# teste01.net
KiCad netlist of a schematic drawn in EAGLE
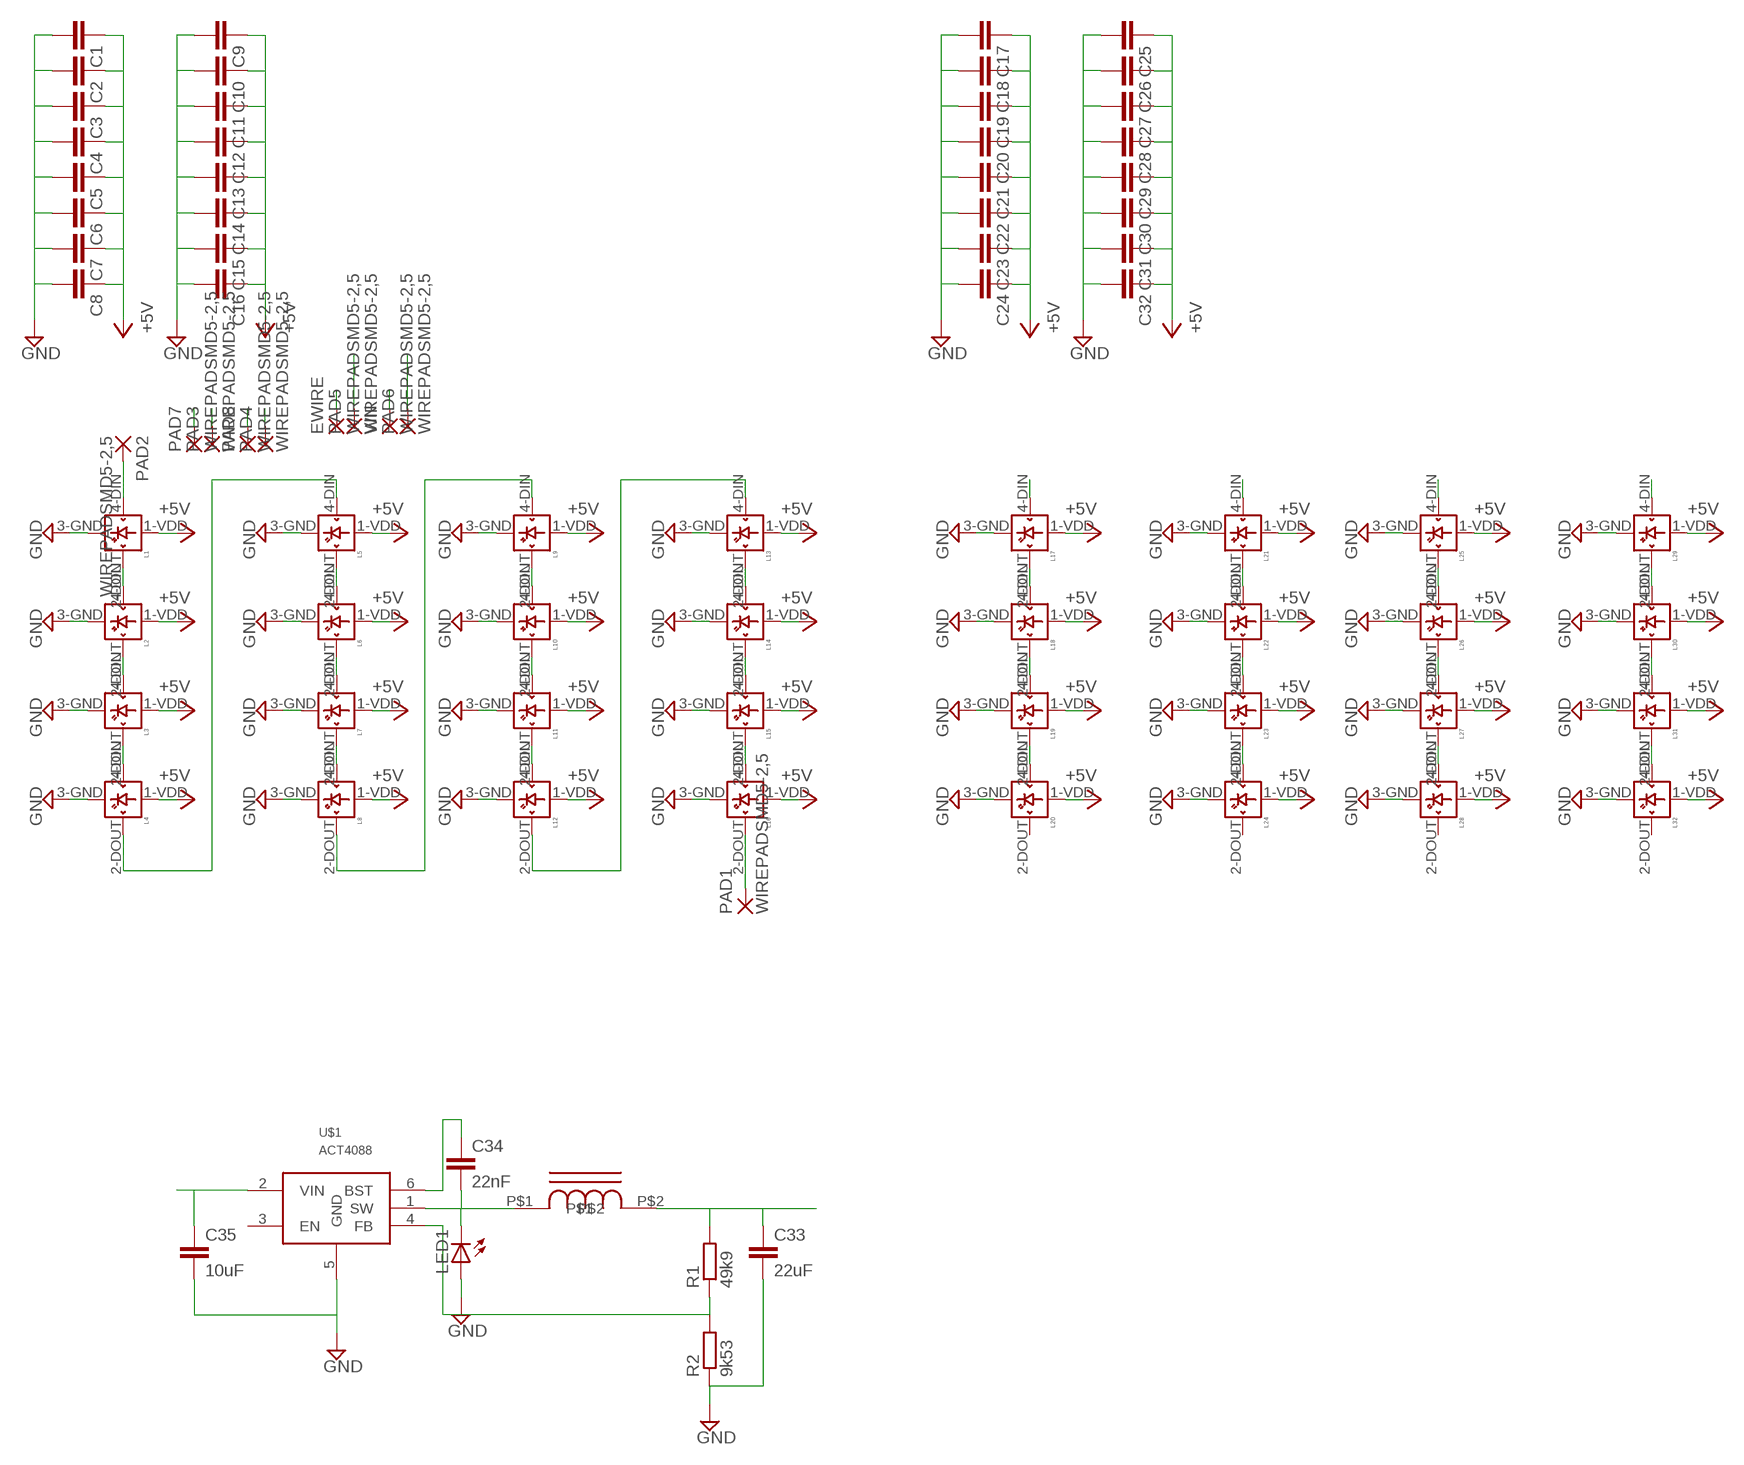
[diagram p0: schematic, sheet 1]

(export (version "E")
  (design (tool "Eeschema 10.0.6"))
  (components
    (comp (ref "C1")
      (value "C-EUC0805K")
      (footprint "eagle-import:C0805K")
      (libsource (lib "eagle-import") (part "resistor_C-EUC0805K"))
    )
    (comp (ref "C2")
      (value "C-EUC0805K")
      (footprint "eagle-import:C0805K")
      (libsource (lib "eagle-import") (part "resistor_C-EUC0805K"))
    )
    (comp (ref "C3")
      (value "C-EUC0805K")
      (footprint "eagle-import:C0805K")
      (libsource (lib "eagle-import") (part "resistor_C-EUC0805K"))
    )
    (comp (ref "C4")
      (value "C-EUC0805K")
      (footprint "eagle-import:C0805K")
      (libsource (lib "eagle-import") (part "resistor_C-EUC0805K"))
    )
    (comp (ref "C5")
      (value "C-EUC0805K")
      (footprint "eagle-import:C0805K")
      (libsource (lib "eagle-import") (part "resistor_C-EUC0805K"))
    )
    (comp (ref "C6")
      (value "C-EUC0805K")
      (footprint "eagle-import:C0805K")
      (libsource (lib "eagle-import") (part "resistor_C-EUC0805K"))
    )
    (comp (ref "C7")
      (value "C-EUC0805K")
      (footprint "eagle-import:C0805K")
      (libsource (lib "eagle-import") (part "resistor_C-EUC0805K"))
    )
    (comp (ref "C8")
      (value "C-EUC0805K")
      (footprint "eagle-import:C0805K")
      (libsource (lib "eagle-import") (part "resistor_C-EUC0805K"))
    )
    (comp (ref "C9")
      (value "C-EUC0805K")
      (footprint "eagle-import:C0805K")
      (libsource (lib "eagle-import") (part "resistor_C-EUC0805K"))
    )
    (comp (ref "C10")
      (value "C-EUC0805K")
      (footprint "eagle-import:C0805K")
      (libsource (lib "eagle-import") (part "resistor_C-EUC0805K"))
    )
    (comp (ref "C11")
      (value "C-EUC0805K")
      (footprint "eagle-import:C0805K")
      (libsource (lib "eagle-import") (part "resistor_C-EUC0805K"))
    )
    (comp (ref "C12")
      (value "C-EUC0805K")
      (footprint "eagle-import:C0805K")
      (libsource (lib "eagle-import") (part "resistor_C-EUC0805K"))
    )
    (comp (ref "C13")
      (value "C-EUC0805K")
      (footprint "eagle-import:C0805K")
      (libsource (lib "eagle-import") (part "resistor_C-EUC0805K"))
    )
    (comp (ref "C14")
      (value "C-EUC0805K")
      (footprint "eagle-import:C0805K")
      (libsource (lib "eagle-import") (part "resistor_C-EUC0805K"))
    )
    (comp (ref "C15")
      (value "C-EUC0805K")
      (footprint "eagle-import:C0805K")
      (libsource (lib "eagle-import") (part "resistor_C-EUC0805K"))
    )
    (comp (ref "C16")
      (value "C-EUC0805K")
      (footprint "eagle-import:C0805K")
      (libsource (lib "eagle-import") (part "resistor_C-EUC0805K"))
    )
    (comp (ref "C17")
      (value "C-EUC0805K")
      (footprint "eagle-import:C0805K")
      (libsource (lib "eagle-import") (part "resistor_C-EUC0805K"))
    )
    (comp (ref "C18")
      (value "C-EUC0805K")
      (footprint "eagle-import:C0805K")
      (libsource (lib "eagle-import") (part "resistor_C-EUC0805K"))
    )
    (comp (ref "C19")
      (value "C-EUC0805K")
      (footprint "eagle-import:C0805K")
      (libsource (lib "eagle-import") (part "resistor_C-EUC0805K"))
    )
    (comp (ref "C20")
      (value "C-EUC0805K")
      (footprint "eagle-import:C0805K")
      (libsource (lib "eagle-import") (part "resistor_C-EUC0805K"))
    )
    (comp (ref "C21")
      (value "C-EUC0805K")
      (footprint "eagle-import:C0805K")
      (libsource (lib "eagle-import") (part "resistor_C-EUC0805K"))
    )
    (comp (ref "C22")
      (value "C-EUC0805K")
      (footprint "eagle-import:C0805K")
      (libsource (lib "eagle-import") (part "resistor_C-EUC0805K"))
    )
    (comp (ref "C23")
      (value "C-EUC0805K")
      (footprint "eagle-import:C0805K")
      (libsource (lib "eagle-import") (part "resistor_C-EUC0805K"))
    )
    (comp (ref "C24")
      (value "C-EUC0805K")
      (footprint "eagle-import:C0805K")
      (libsource (lib "eagle-import") (part "resistor_C-EUC0805K"))
    )
    (comp (ref "C25")
      (value "C-EUC0805K")
      (footprint "eagle-import:C0805K")
      (libsource (lib "eagle-import") (part "resistor_C-EUC0805K"))
    )
    (comp (ref "C26")
      (value "C-EUC0805K")
      (footprint "eagle-import:C0805K")
      (libsource (lib "eagle-import") (part "resistor_C-EUC0805K"))
    )
    (comp (ref "C27")
      (value "C-EUC0805K")
      (footprint "eagle-import:C0805K")
      (libsource (lib "eagle-import") (part "resistor_C-EUC0805K"))
    )
    (comp (ref "C28")
      (value "C-EUC0805K")
      (footprint "eagle-import:C0805K")
      (libsource (lib "eagle-import") (part "resistor_C-EUC0805K"))
    )
    (comp (ref "C29")
      (value "C-EUC0805K")
      (footprint "eagle-import:C0805K")
      (libsource (lib "eagle-import") (part "resistor_C-EUC0805K"))
    )
    (comp (ref "C30")
      (value "C-EUC0805K")
      (footprint "eagle-import:C0805K")
      (libsource (lib "eagle-import") (part "resistor_C-EUC0805K"))
    )
    (comp (ref "C31")
      (value "C-EUC0805K")
      (footprint "eagle-import:C0805K")
      (libsource (lib "eagle-import") (part "resistor_C-EUC0805K"))
    )
    (comp (ref "C32")
      (value "C-EUC0805K")
      (footprint "eagle-import:C0805K")
      (libsource (lib "eagle-import") (part "resistor_C-EUC0805K"))
    )
    (comp (ref "C33")
      (value "22uF")
      (footprint "eagle-import:C1210")
      (libsource (lib "eagle-import") (part "C-EUC1210"))
    )
    (comp (ref "C34")
      (value "22nF")
      (footprint "eagle-import:C0805")
      (libsource (lib "eagle-import") (part "resistor_C-EUC0805"))
    )
    (comp (ref "C35")
      (value "10uF")
      (footprint "eagle-import:C1210")
      (libsource (lib "eagle-import") (part "C-EUC1210"))
    )
    (comp (ref "EWIRE")
      (value "WIREPADSMD5-2,5")
      (footprint "eagle-import:5-2,5")
      (libsource (lib "eagle-import") (part "WIREPADSMD5-2,5"))
    )
    (comp (ref "L1")
      (value "WS2812B")
      (footprint "eagle-import:WS2812B")
      (libsource (lib "eagle-import") (part "WS2812B"))
    )
    (comp (ref "L2")
      (value "WS2812B")
      (footprint "eagle-import:WS2812B")
      (libsource (lib "eagle-import") (part "WS2812B"))
    )
    (comp (ref "L3")
      (value "WS2812B")
      (footprint "eagle-import:WS2812B")
      (libsource (lib "eagle-import") (part "WS2812B"))
    )
    (comp (ref "L4")
      (value "WS2812B")
      (footprint "eagle-import:WS2812B")
      (libsource (lib "eagle-import") (part "WS2812B"))
    )
    (comp (ref "L5")
      (value "WS2812B")
      (footprint "eagle-import:WS2812B")
      (libsource (lib "eagle-import") (part "WS2812B"))
    )
    (comp (ref "L6")
      (value "WS2812B")
      (footprint "eagle-import:WS2812B")
      (libsource (lib "eagle-import") (part "WS2812B"))
    )
    (comp (ref "L7")
      (value "WS2812B")
      (footprint "eagle-import:WS2812B")
      (libsource (lib "eagle-import") (part "WS2812B"))
    )
    (comp (ref "L8")
      (value "WS2812B")
      (footprint "eagle-import:WS2812B")
      (libsource (lib "eagle-import") (part "WS2812B"))
    )
    (comp (ref "L9")
      (value "WS2812B")
      (footprint "eagle-import:WS2812B")
      (libsource (lib "eagle-import") (part "WS2812B"))
    )
    (comp (ref "L10")
      (value "WS2812B")
      (footprint "eagle-import:WS2812B")
      (libsource (lib "eagle-import") (part "WS2812B"))
    )
    (comp (ref "L11")
      (value "WS2812B")
      (footprint "eagle-import:WS2812B")
      (libsource (lib "eagle-import") (part "WS2812B"))
    )
    (comp (ref "L12")
      (value "WS2812B")
      (footprint "eagle-import:WS2812B")
      (libsource (lib "eagle-import") (part "WS2812B"))
    )
    (comp (ref "L13")
      (value "WS2812B")
      (footprint "eagle-import:WS2812B")
      (libsource (lib "eagle-import") (part "WS2812B"))
    )
    (comp (ref "L14")
      (value "WS2812B")
      (footprint "eagle-import:WS2812B")
      (libsource (lib "eagle-import") (part "WS2812B"))
    )
    (comp (ref "L15")
      (value "WS2812B")
      (footprint "eagle-import:WS2812B")
      (libsource (lib "eagle-import") (part "WS2812B"))
    )
    (comp (ref "L16")
      (value "WS2812B")
      (footprint "eagle-import:WS2812B")
      (libsource (lib "eagle-import") (part "WS2812B"))
    )
    (comp (ref "L17")
      (value "WS2812B")
      (footprint "eagle-import:WS2812B")
      (libsource (lib "eagle-import") (part "WS2812B"))
    )
    (comp (ref "L18")
      (value "WS2812B")
      (footprint "eagle-import:WS2812B")
      (libsource (lib "eagle-import") (part "WS2812B"))
    )
    (comp (ref "L19")
      (value "WS2812B")
      (footprint "eagle-import:WS2812B")
      (libsource (lib "eagle-import") (part "WS2812B"))
    )
    (comp (ref "L20")
      (value "WS2812B")
      (footprint "eagle-import:WS2812B")
      (libsource (lib "eagle-import") (part "WS2812B"))
    )
    (comp (ref "L21")
      (value "WS2812B")
      (footprint "eagle-import:WS2812B")
      (libsource (lib "eagle-import") (part "WS2812B"))
    )
    (comp (ref "L22")
      (value "WS2812B")
      (footprint "eagle-import:WS2812B")
      (libsource (lib "eagle-import") (part "WS2812B"))
    )
    (comp (ref "L23")
      (value "WS2812B")
      (footprint "eagle-import:WS2812B")
      (libsource (lib "eagle-import") (part "WS2812B"))
    )
    (comp (ref "L24")
      (value "WS2812B")
      (footprint "eagle-import:WS2812B")
      (libsource (lib "eagle-import") (part "WS2812B"))
    )
    (comp (ref "L25")
      (value "WS2812B")
      (footprint "eagle-import:WS2812B")
      (libsource (lib "eagle-import") (part "WS2812B"))
    )
    (comp (ref "L26")
      (value "WS2812B")
      (footprint "eagle-import:WS2812B")
      (libsource (lib "eagle-import") (part "WS2812B"))
    )
    (comp (ref "L27")
      (value "WS2812B")
      (footprint "eagle-import:WS2812B")
      (libsource (lib "eagle-import") (part "WS2812B"))
    )
    (comp (ref "L28")
      (value "WS2812B")
      (footprint "eagle-import:WS2812B")
      (libsource (lib "eagle-import") (part "WS2812B"))
    )
    (comp (ref "L29")
      (value "WS2812B")
      (footprint "eagle-import:WS2812B")
      (libsource (lib "eagle-import") (part "WS2812B"))
    )
    (comp (ref "L30")
      (value "WS2812B")
      (footprint "eagle-import:WS2812B")
      (libsource (lib "eagle-import") (part "WS2812B"))
    )
    (comp (ref "L31")
      (value "WS2812B")
      (footprint "eagle-import:WS2812B")
      (libsource (lib "eagle-import") (part "WS2812B"))
    )
    (comp (ref "L32")
      (value "WS2812B")
      (footprint "eagle-import:WS2812B")
      (libsource (lib "eagle-import") (part "WS2812B"))
    )
    (comp (ref "LED1")
      (value "LED1206")
      (footprint "eagle-import:LED-1206")
      (libsource (lib "eagle-import") (part "LED1206"))
    )
    (comp (ref "PAD1")
      (value "WIREPADSMD5-2,5")
      (footprint "eagle-import:5-2,5")
      (libsource (lib "eagle-import") (part "WIREPADSMD5-2,5"))
    )
    (comp (ref "PAD2")
      (value "WIREPADSMD5-2,5")
      (footprint "eagle-import:5-2,5")
      (libsource (lib "eagle-import") (part "WIREPADSMD5-2,5"))
    )
    (comp (ref "PAD3")
      (value "WIREPADSMD5-2,5")
      (footprint "eagle-import:5-2,5")
      (libsource (lib "eagle-import") (part "WIREPADSMD5-2,5"))
    )
    (comp (ref "PAD4")
      (value "WIREPADSMD5-2,5")
      (footprint "eagle-import:5-2,5")
      (libsource (lib "eagle-import") (part "WIREPADSMD5-2,5"))
    )
    (comp (ref "PAD5")
      (value "WIREPADSMD5-2,5")
      (footprint "eagle-import:5-2,5")
      (libsource (lib "eagle-import") (part "WIREPADSMD5-2,5"))
    )
    (comp (ref "PAD6")
      (value "WIREPADSMD5-2,5")
      (footprint "eagle-import:5-2,5")
      (libsource (lib "eagle-import") (part "WIREPADSMD5-2,5"))
    )
    (comp (ref "PAD7")
      (value "WIREPADSMD5-2,5")
      (footprint "eagle-import:5-2,5")
      (libsource (lib "eagle-import") (part "WIREPADSMD5-2,5"))
    )
    (comp (ref "PAD8")
      (value "WIREPADSMD5-2,5")
      (footprint "eagle-import:5-2,5")
      (libsource (lib "eagle-import") (part "WIREPADSMD5-2,5"))
    )
    (comp (ref "R1")
      (value "49k9")
      (footprint "eagle-import:M0805")
      (libsource (lib "eagle-import") (part "R-EU_M0805"))
    )
    (comp (ref "R2")
      (value "9k53")
      (footprint "eagle-import:M0805")
      (libsource (lib "eagle-import") (part "R-EU_M0805"))
    )
    (comp (ref "U$1")
      (value "ACT4088")
      (footprint "eagle-import:SOT23-6")
      (libsource (lib "eagle-import") (part "ACT4088"))
    )
    (comp (ref "U$2")
      (value "INDUCTOR")
      (footprint "eagle-import:6060")
      (libsource (lib "eagle-import") (part "INDUCTOR"))
    )
    (comp (ref "VIN")
      (value "WIREPADSMD5-2,5")
      (footprint "eagle-import:5-2,5")
      (libsource (lib "eagle-import") (part "WIREPADSMD5-2,5"))
    )
  )
  (nets
    (net (code "1") (name "+5V") (class "Default")
      (node (ref "C1") (pin "1") (pinfunction "1_1") (pintype "passive"))
      (node (ref "C10") (pin "1") (pinfunction "1_1") (pintype "passive"))
      (node (ref "C11") (pin "1") (pinfunction "1_1") (pintype "passive"))
      (node (ref "C12") (pin "1") (pinfunction "1_1") (pintype "passive"))
      (node (ref "C13") (pin "1") (pinfunction "1_1") (pintype "passive"))
      (node (ref "C14") (pin "1") (pinfunction "1_1") (pintype "passive"))
      (node (ref "C15") (pin "1") (pinfunction "1_1") (pintype "passive"))
      (node (ref "C16") (pin "1") (pinfunction "1_1") (pintype "passive"))
      (node (ref "C17") (pin "1") (pinfunction "1_1") (pintype "passive"))
      (node (ref "C18") (pin "1") (pinfunction "1_1") (pintype "passive"))
      (node (ref "C19") (pin "1") (pinfunction "1_1") (pintype "passive"))
      (node (ref "C2") (pin "1") (pinfunction "1_1") (pintype "passive"))
      (node (ref "C20") (pin "1") (pinfunction "1_1") (pintype "passive"))
      (node (ref "C21") (pin "1") (pinfunction "1_1") (pintype "passive"))
      (node (ref "C22") (pin "1") (pinfunction "1_1") (pintype "passive"))
      (node (ref "C23") (pin "1") (pinfunction "1_1") (pintype "passive"))
      (node (ref "C24") (pin "1") (pinfunction "1_1") (pintype "passive"))
      (node (ref "C25") (pin "1") (pinfunction "1_1") (pintype "passive"))
      (node (ref "C26") (pin "1") (pinfunction "1_1") (pintype "passive"))
      (node (ref "C27") (pin "1") (pinfunction "1_1") (pintype "passive"))
      (node (ref "C28") (pin "1") (pinfunction "1_1") (pintype "passive"))
      (node (ref "C29") (pin "1") (pinfunction "1_1") (pintype "passive"))
      (node (ref "C3") (pin "1") (pinfunction "1_1") (pintype "passive"))
      (node (ref "C30") (pin "1") (pinfunction "1_1") (pintype "passive"))
      (node (ref "C31") (pin "1") (pinfunction "1_1") (pintype "passive"))
      (node (ref "C32") (pin "1") (pinfunction "1_1") (pintype "passive"))
      (node (ref "C4") (pin "1") (pinfunction "1_1") (pintype "passive"))
      (node (ref "C5") (pin "1") (pinfunction "1_1") (pintype "passive"))
      (node (ref "C6") (pin "1") (pinfunction "1_1") (pintype "passive"))
      (node (ref "C7") (pin "1") (pinfunction "1_1") (pintype "passive"))
      (node (ref "C8") (pin "1") (pinfunction "1_1") (pintype "passive"))
      (node (ref "C9") (pin "1") (pinfunction "1_1") (pintype "passive"))
      (node (ref "L1") (pin "1-VDD") (pinfunction "VDD_1-VDD") (pintype "bidirectional"))
      (node (ref "L10") (pin "1-VDD") (pinfunction "VDD_1-VDD") (pintype "bidirectional"))
      (node (ref "L11") (pin "1-VDD") (pinfunction "VDD_1-VDD") (pintype "bidirectional"))
      (node (ref "L12") (pin "1-VDD") (pinfunction "VDD_1-VDD") (pintype "bidirectional"))
      (node (ref "L13") (pin "1-VDD") (pinfunction "VDD_1-VDD") (pintype "bidirectional"))
      (node (ref "L14") (pin "1-VDD") (pinfunction "VDD_1-VDD") (pintype "bidirectional"))
      (node (ref "L15") (pin "1-VDD") (pinfunction "VDD_1-VDD") (pintype "bidirectional"))
      (node (ref "L16") (pin "1-VDD") (pinfunction "VDD_1-VDD") (pintype "bidirectional"))
      (node (ref "L17") (pin "1-VDD") (pinfunction "VDD_1-VDD") (pintype "bidirectional"))
      (node (ref "L18") (pin "1-VDD") (pinfunction "VDD_1-VDD") (pintype "bidirectional"))
      (node (ref "L19") (pin "1-VDD") (pinfunction "VDD_1-VDD") (pintype "bidirectional"))
      (node (ref "L2") (pin "1-VDD") (pinfunction "VDD_1-VDD") (pintype "bidirectional"))
      (node (ref "L20") (pin "1-VDD") (pinfunction "VDD_1-VDD") (pintype "bidirectional"))
      (node (ref "L21") (pin "1-VDD") (pinfunction "VDD_1-VDD") (pintype "bidirectional"))
      (node (ref "L22") (pin "1-VDD") (pinfunction "VDD_1-VDD") (pintype "bidirectional"))
      (node (ref "L23") (pin "1-VDD") (pinfunction "VDD_1-VDD") (pintype "bidirectional"))
      (node (ref "L24") (pin "1-VDD") (pinfunction "VDD_1-VDD") (pintype "bidirectional"))
      (node (ref "L25") (pin "1-VDD") (pinfunction "VDD_1-VDD") (pintype "bidirectional"))
      (node (ref "L26") (pin "1-VDD") (pinfunction "VDD_1-VDD") (pintype "bidirectional"))
      (node (ref "L27") (pin "1-VDD") (pinfunction "VDD_1-VDD") (pintype "bidirectional"))
      (node (ref "L28") (pin "1-VDD") (pinfunction "VDD_1-VDD") (pintype "bidirectional"))
      (node (ref "L29") (pin "1-VDD") (pinfunction "VDD_1-VDD") (pintype "bidirectional"))
      (node (ref "L3") (pin "1-VDD") (pinfunction "VDD_1-VDD") (pintype "bidirectional"))
      (node (ref "L30") (pin "1-VDD") (pinfunction "VDD_1-VDD") (pintype "bidirectional"))
      (node (ref "L31") (pin "1-VDD") (pinfunction "VDD_1-VDD") (pintype "bidirectional"))
      (node (ref "L32") (pin "1-VDD") (pinfunction "VDD_1-VDD") (pintype "bidirectional"))
      (node (ref "L4") (pin "1-VDD") (pinfunction "VDD_1-VDD") (pintype "bidirectional"))
      (node (ref "L5") (pin "1-VDD") (pinfunction "VDD_1-VDD") (pintype "bidirectional"))
      (node (ref "L6") (pin "1-VDD") (pinfunction "VDD_1-VDD") (pintype "bidirectional"))
      (node (ref "L7") (pin "1-VDD") (pinfunction "VDD_1-VDD") (pintype "bidirectional"))
      (node (ref "L8") (pin "1-VDD") (pinfunction "VDD_1-VDD") (pintype "bidirectional"))
      (node (ref "L9") (pin "1-VDD") (pinfunction "VDD_1-VDD") (pintype "bidirectional"))
    )
    (net (code "2") (name "/VIN") (class "Default")
      (node (ref "C35") (pin "1") (pinfunction "1_1") (pintype "passive"))
      (node (ref "EWIRE") (pin "1") (pinfunction "P_1") (pintype "passive"))
      (node (ref "PAD5") (pin "1") (pinfunction "P_1") (pintype "passive"))
      (node (ref "PAD6") (pin "1") (pinfunction "P_1") (pintype "passive"))
      (node (ref "U$1") (pin "2") (pinfunction "VIN_2") (pintype "bidirectional"))
      (node (ref "VIN") (pin "1") (pinfunction "P_1") (pintype "passive"))
    )
    (net (code "3") (name "GND") (class "Default")
      (node (ref "C1") (pin "2") (pinfunction "2_2") (pintype "passive"))
      (node (ref "C10") (pin "2") (pinfunction "2_2") (pintype "passive"))
      (node (ref "C11") (pin "2") (pinfunction "2_2") (pintype "passive"))
      (node (ref "C12") (pin "2") (pinfunction "2_2") (pintype "passive"))
      (node (ref "C13") (pin "2") (pinfunction "2_2") (pintype "passive"))
      (node (ref "C14") (pin "2") (pinfunction "2_2") (pintype "passive"))
      (node (ref "C15") (pin "2") (pinfunction "2_2") (pintype "passive"))
      (node (ref "C16") (pin "2") (pinfunction "2_2") (pintype "passive"))
      (node (ref "C17") (pin "2") (pinfunction "2_2") (pintype "passive"))
      (node (ref "C18") (pin "2") (pinfunction "2_2") (pintype "passive"))
      (node (ref "C19") (pin "2") (pinfunction "2_2") (pintype "passive"))
      (node (ref "C2") (pin "2") (pinfunction "2_2") (pintype "passive"))
      (node (ref "C20") (pin "2") (pinfunction "2_2") (pintype "passive"))
      (node (ref "C21") (pin "2") (pinfunction "2_2") (pintype "passive"))
      (node (ref "C22") (pin "2") (pinfunction "2_2") (pintype "passive"))
      (node (ref "C23") (pin "2") (pinfunction "2_2") (pintype "passive"))
      (node (ref "C24") (pin "2") (pinfunction "2_2") (pintype "passive"))
      (node (ref "C25") (pin "2") (pinfunction "2_2") (pintype "passive"))
      (node (ref "C26") (pin "2") (pinfunction "2_2") (pintype "passive"))
      (node (ref "C27") (pin "2") (pinfunction "2_2") (pintype "passive"))
      (node (ref "C28") (pin "2") (pinfunction "2_2") (pintype "passive"))
      (node (ref "C29") (pin "2") (pinfunction "2_2") (pintype "passive"))
      (node (ref "C3") (pin "2") (pinfunction "2_2") (pintype "passive"))
      (node (ref "C30") (pin "2") (pinfunction "2_2") (pintype "passive"))
      (node (ref "C31") (pin "2") (pinfunction "2_2") (pintype "passive"))
      (node (ref "C32") (pin "2") (pinfunction "2_2") (pintype "passive"))
      (node (ref "C33") (pin "2") (pinfunction "2_2") (pintype "passive"))
      (node (ref "C35") (pin "2") (pinfunction "2_2") (pintype "passive"))
      (node (ref "C4") (pin "2") (pinfunction "2_2") (pintype "passive"))
      (node (ref "C5") (pin "2") (pinfunction "2_2") (pintype "passive"))
      (node (ref "C6") (pin "2") (pinfunction "2_2") (pintype "passive"))
      (node (ref "C7") (pin "2") (pinfunction "2_2") (pintype "passive"))
      (node (ref "C8") (pin "2") (pinfunction "2_2") (pintype "passive"))
      (node (ref "C9") (pin "2") (pinfunction "2_2") (pintype "passive"))
      (node (ref "L1") (pin "3-GND") (pinfunction "GND_3-GND") (pintype "bidirectional"))
      (node (ref "L10") (pin "3-GND") (pinfunction "GND_3-GND") (pintype "bidirectional"))
      (node (ref "L11") (pin "3-GND") (pinfunction "GND_3-GND") (pintype "bidirectional"))
      (node (ref "L12") (pin "3-GND") (pinfunction "GND_3-GND") (pintype "bidirectional"))
      (node (ref "L13") (pin "3-GND") (pinfunction "GND_3-GND") (pintype "bidirectional"))
      (node (ref "L14") (pin "3-GND") (pinfunction "GND_3-GND") (pintype "bidirectional"))
      (node (ref "L15") (pin "3-GND") (pinfunction "GND_3-GND") (pintype "bidirectional"))
      (node (ref "L16") (pin "3-GND") (pinfunction "GND_3-GND") (pintype "bidirectional"))
      (node (ref "L17") (pin "3-GND") (pinfunction "GND_3-GND") (pintype "bidirectional"))
      (node (ref "L18") (pin "3-GND") (pinfunction "GND_3-GND") (pintype "bidirectional"))
      (node (ref "L19") (pin "3-GND") (pinfunction "GND_3-GND") (pintype "bidirectional"))
      (node (ref "L2") (pin "3-GND") (pinfunction "GND_3-GND") (pintype "bidirectional"))
      (node (ref "L20") (pin "3-GND") (pinfunction "GND_3-GND") (pintype "bidirectional"))
      (node (ref "L21") (pin "3-GND") (pinfunction "GND_3-GND") (pintype "bidirectional"))
      (node (ref "L22") (pin "3-GND") (pinfunction "GND_3-GND") (pintype "bidirectional"))
      (node (ref "L23") (pin "3-GND") (pinfunction "GND_3-GND") (pintype "bidirectional"))
      (node (ref "L24") (pin "3-GND") (pinfunction "GND_3-GND") (pintype "bidirectional"))
      (node (ref "L25") (pin "3-GND") (pinfunction "GND_3-GND") (pintype "bidirectional"))
      (node (ref "L26") (pin "3-GND") (pinfunction "GND_3-GND") (pintype "bidirectional"))
      (node (ref "L27") (pin "3-GND") (pinfunction "GND_3-GND") (pintype "bidirectional"))
      (node (ref "L28") (pin "3-GND") (pinfunction "GND_3-GND") (pintype "bidirectional"))
      (node (ref "L29") (pin "3-GND") (pinfunction "GND_3-GND") (pintype "bidirectional"))
      (node (ref "L3") (pin "3-GND") (pinfunction "GND_3-GND") (pintype "bidirectional"))
      (node (ref "L30") (pin "3-GND") (pinfunction "GND_3-GND") (pintype "bidirectional"))
      (node (ref "L31") (pin "3-GND") (pinfunction "GND_3-GND") (pintype "bidirectional"))
      (node (ref "L32") (pin "3-GND") (pinfunction "GND_3-GND") (pintype "bidirectional"))
      (node (ref "L4") (pin "3-GND") (pinfunction "GND_3-GND") (pintype "bidirectional"))
      (node (ref "L5") (pin "3-GND") (pinfunction "GND_3-GND") (pintype "bidirectional"))
      (node (ref "L6") (pin "3-GND") (pinfunction "GND_3-GND") (pintype "bidirectional"))
      (node (ref "L7") (pin "3-GND") (pinfunction "GND_3-GND") (pintype "bidirectional"))
      (node (ref "L8") (pin "3-GND") (pinfunction "GND_3-GND") (pintype "bidirectional"))
      (node (ref "L9") (pin "3-GND") (pinfunction "GND_3-GND") (pintype "bidirectional"))
      (node (ref "LED1") (pin "A") (pinfunction "A_A") (pintype "passive"))
      (node (ref "PAD3") (pin "1") (pinfunction "P_1") (pintype "passive"))
      (node (ref "PAD4") (pin "1") (pinfunction "P_1") (pintype "passive"))
      (node (ref "PAD7") (pin "1") (pinfunction "P_1") (pintype "passive"))
      (node (ref "PAD8") (pin "1") (pinfunction "P_1") (pintype "passive"))
      (node (ref "R2") (pin "1") (pinfunction "1_1") (pintype "passive"))
      (node (ref "U$1") (pin "5") (pinfunction "GND_5") (pintype "bidirectional"))
    )
    (net (code "4") (name "Net-(C33-Pad1)") (class "Default")
      (node (ref "C33") (pin "1") (pinfunction "1_1") (pintype "passive"))
      (node (ref "R1") (pin "2") (pinfunction "2_2") (pintype "passive"))
      (node (ref "U$2") (pin "P$2") (pinfunction "P$2_P$2") (pintype "bidirectional"))
    )
    (net (code "5") (name "Net-(L1-DIN)") (class "Default")
      (node (ref "L1") (pin "4-DIN") (pinfunction "DIN_4-DIN") (pintype "input"))
      (node (ref "PAD2") (pin "1") (pinfunction "P_1") (pintype "passive"))
    )
    (net (code "6") (name "Net-(L1-DOUT)") (class "Default")
      (node (ref "L1") (pin "2-DOUT") (pinfunction "DOUT_2-DOUT") (pintype "output"))
      (node (ref "L2") (pin "4-DIN") (pinfunction "DIN_4-DIN") (pintype "input"))
    )
    (net (code "7") (name "Net-(L2-DOUT)") (class "Default")
      (node (ref "L2") (pin "2-DOUT") (pinfunction "DOUT_2-DOUT") (pintype "output"))
      (node (ref "L3") (pin "4-DIN") (pinfunction "DIN_4-DIN") (pintype "input"))
    )
    (net (code "8") (name "Net-(L3-DOUT)") (class "Default")
      (node (ref "L3") (pin "2-DOUT") (pinfunction "DOUT_2-DOUT") (pintype "output"))
      (node (ref "L4") (pin "4-DIN") (pinfunction "DIN_4-DIN") (pintype "input"))
    )
    (net (code "9") (name "Net-(L4-DOUT)") (class "Default")
      (node (ref "L4") (pin "2-DOUT") (pinfunction "DOUT_2-DOUT") (pintype "output"))
      (node (ref "L5") (pin "4-DIN") (pinfunction "DIN_4-DIN") (pintype "input"))
    )
    (net (code "10") (name "Net-(L5-DOUT)") (class "Default")
      (node (ref "L5") (pin "2-DOUT") (pinfunction "DOUT_2-DOUT") (pintype "output"))
      (node (ref "L6") (pin "4-DIN") (pinfunction "DIN_4-DIN") (pintype "input"))
    )
    (net (code "11") (name "Net-(L6-DOUT)") (class "Default")
      (node (ref "L6") (pin "2-DOUT") (pinfunction "DOUT_2-DOUT") (pintype "output"))
      (node (ref "L7") (pin "4-DIN") (pinfunction "DIN_4-DIN") (pintype "input"))
    )
    (net (code "12") (name "Net-(L7-DOUT)") (class "Default")
      (node (ref "L7") (pin "2-DOUT") (pinfunction "DOUT_2-DOUT") (pintype "output"))
      (node (ref "L8") (pin "4-DIN") (pinfunction "DIN_4-DIN") (pintype "input"))
    )
    (net (code "13") (name "Net-(L8-DOUT)") (class "Default")
      (node (ref "L8") (pin "2-DOUT") (pinfunction "DOUT_2-DOUT") (pintype "output"))
      (node (ref "L9") (pin "4-DIN") (pinfunction "DIN_4-DIN") (pintype "input"))
    )
    (net (code "14") (name "Net-(L10-DIN)") (class "Default")
      (node (ref "L10") (pin "4-DIN") (pinfunction "DIN_4-DIN") (pintype "input"))
      (node (ref "L9") (pin "2-DOUT") (pinfunction "DOUT_2-DOUT") (pintype "output"))
    )
    (net (code "15") (name "Net-(L10-DOUT)") (class "Default")
      (node (ref "L10") (pin "2-DOUT") (pinfunction "DOUT_2-DOUT") (pintype "output"))
      (node (ref "L11") (pin "4-DIN") (pinfunction "DIN_4-DIN") (pintype "input"))
    )
    (net (code "16") (name "Net-(L11-DOUT)") (class "Default")
      (node (ref "L11") (pin "2-DOUT") (pinfunction "DOUT_2-DOUT") (pintype "output"))
      (node (ref "L12") (pin "4-DIN") (pinfunction "DIN_4-DIN") (pintype "input"))
    )
    (net (code "17") (name "Net-(L12-DOUT)") (class "Default")
      (node (ref "L12") (pin "2-DOUT") (pinfunction "DOUT_2-DOUT") (pintype "output"))
      (node (ref "L13") (pin "4-DIN") (pinfunction "DIN_4-DIN") (pintype "input"))
    )
    (net (code "18") (name "Net-(L13-DOUT)") (class "Default")
      (node (ref "L13") (pin "2-DOUT") (pinfunction "DOUT_2-DOUT") (pintype "output"))
      (node (ref "L14") (pin "4-DIN") (pinfunction "DIN_4-DIN") (pintype "input"))
    )
    (net (code "19") (name "Net-(L14-DOUT)") (class "Default")
      (node (ref "L14") (pin "2-DOUT") (pinfunction "DOUT_2-DOUT") (pintype "output"))
      (node (ref "L15") (pin "4-DIN") (pinfunction "DIN_4-DIN") (pintype "input"))
    )
    (net (code "20") (name "Net-(L15-DOUT)") (class "Default")
      (node (ref "L15") (pin "2-DOUT") (pinfunction "DOUT_2-DOUT") (pintype "output"))
      (node (ref "L16") (pin "4-DIN") (pinfunction "DIN_4-DIN") (pintype "input"))
    )
    (net (code "21") (name "Net-(L16-DOUT)") (class "Default")
      (node (ref "L16") (pin "2-DOUT") (pinfunction "DOUT_2-DOUT") (pintype "output"))
      (node (ref "PAD1") (pin "1") (pinfunction "P_1") (pintype "passive"))
    )
    (net (code "22") (name "Net-(L17-DOUT)") (class "Default")
      (node (ref "L17") (pin "2-DOUT") (pinfunction "DOUT_2-DOUT") (pintype "output"))
      (node (ref "L18") (pin "4-DIN") (pinfunction "DIN_4-DIN") (pintype "input"))
    )
    (net (code "23") (name "Net-(L18-DOUT)") (class "Default")
      (node (ref "L18") (pin "2-DOUT") (pinfunction "DOUT_2-DOUT") (pintype "output"))
      (node (ref "L19") (pin "4-DIN") (pinfunction "DIN_4-DIN") (pintype "input"))
    )
    (net (code "24") (name "Net-(L19-DOUT)") (class "Default")
      (node (ref "L19") (pin "2-DOUT") (pinfunction "DOUT_2-DOUT") (pintype "output"))
      (node (ref "L20") (pin "4-DIN") (pinfunction "DIN_4-DIN") (pintype "input"))
    )
    (net (code "25") (name "Net-(L21-DOUT)") (class "Default")
      (node (ref "L21") (pin "2-DOUT") (pinfunction "DOUT_2-DOUT") (pintype "output"))
      (node (ref "L22") (pin "4-DIN") (pinfunction "DIN_4-DIN") (pintype "input"))
    )
    (net (code "26") (name "Net-(L22-DOUT)") (class "Default")
      (node (ref "L22") (pin "2-DOUT") (pinfunction "DOUT_2-DOUT") (pintype "output"))
      (node (ref "L23") (pin "4-DIN") (pinfunction "DIN_4-DIN") (pintype "input"))
    )
    (net (code "27") (name "Net-(L23-DOUT)") (class "Default")
      (node (ref "L23") (pin "2-DOUT") (pinfunction "DOUT_2-DOUT") (pintype "output"))
      (node (ref "L24") (pin "4-DIN") (pinfunction "DIN_4-DIN") (pintype "input"))
    )
    (net (code "28") (name "Net-(L25-DOUT)") (class "Default")
      (node (ref "L25") (pin "2-DOUT") (pinfunction "DOUT_2-DOUT") (pintype "output"))
      (node (ref "L26") (pin "4-DIN") (pinfunction "DIN_4-DIN") (pintype "input"))
    )
    (net (code "29") (name "Net-(L26-DOUT)") (class "Default")
      (node (ref "L26") (pin "2-DOUT") (pinfunction "DOUT_2-DOUT") (pintype "output"))
      (node (ref "L27") (pin "4-DIN") (pinfunction "DIN_4-DIN") (pintype "input"))
    )
    (net (code "30") (name "Net-(L27-DOUT)") (class "Default")
      (node (ref "L27") (pin "2-DOUT") (pinfunction "DOUT_2-DOUT") (pintype "output"))
      (node (ref "L28") (pin "4-DIN") (pinfunction "DIN_4-DIN") (pintype "input"))
    )
    (net (code "31") (name "Net-(L29-DOUT)") (class "Default")
      (node (ref "L29") (pin "2-DOUT") (pinfunction "DOUT_2-DOUT") (pintype "output"))
      (node (ref "L30") (pin "4-DIN") (pinfunction "DIN_4-DIN") (pintype "input"))
    )
    (net (code "32") (name "Net-(L30-DOUT)") (class "Default")
      (node (ref "L30") (pin "2-DOUT") (pinfunction "DOUT_2-DOUT") (pintype "output"))
      (node (ref "L31") (pin "4-DIN") (pinfunction "DIN_4-DIN") (pintype "input"))
    )
    (net (code "33") (name "Net-(L31-DOUT)") (class "Default")
      (node (ref "L31") (pin "2-DOUT") (pinfunction "DOUT_2-DOUT") (pintype "output"))
      (node (ref "L32") (pin "4-DIN") (pinfunction "DIN_4-DIN") (pintype "input"))
    )
    (net (code "34") (name "Net-(U$1-BST)") (class "Default")
      (node (ref "C34") (pin "1") (pinfunction "1_1") (pintype "passive"))
      (node (ref "U$1") (pin "6") (pinfunction "BST_6") (pintype "bidirectional"))
    )
    (net (code "35") (name "Net-(U$1-FB)") (class "Default")
      (node (ref "R1") (pin "1") (pinfunction "1_1") (pintype "passive"))
      (node (ref "R2") (pin "2") (pinfunction "2_2") (pintype "passive"))
      (node (ref "U$1") (pin "4") (pinfunction "FB_4") (pintype "bidirectional"))
    )
    (net (code "36") (name "Net-(U$1-SW)") (class "Default")
      (node (ref "C34") (pin "2") (pinfunction "2_2") (pintype "passive"))
      (node (ref "LED1") (pin "C") (pinfunction "C_C") (pintype "passive"))
      (node (ref "U$1") (pin "1") (pinfunction "SW_1") (pintype "bidirectional"))
      (node (ref "U$2") (pin "P$1") (pinfunction "P$1_P$1") (pintype "bidirectional"))
    )
    (net (code "37") (name "unconnected-(L17-DIN-Pad4-DIN)") (class "Default")
      (node (ref "L17") (pin "4-DIN") (pinfunction "DIN_4-DIN") (pintype "input"))
    )
    (net (code "38") (name "unconnected-(L20-DOUT-Pad2-DOUT)") (class "Default")
      (node (ref "L20") (pin "2-DOUT") (pinfunction "DOUT_2-DOUT") (pintype "output"))
    )
    (net (code "39") (name "unconnected-(L21-DIN-Pad4-DIN)") (class "Default")
      (node (ref "L21") (pin "4-DIN") (pinfunction "DIN_4-DIN") (pintype "input"))
    )
    (net (code "40") (name "unconnected-(L24-DOUT-Pad2-DOUT)") (class "Default")
      (node (ref "L24") (pin "2-DOUT") (pinfunction "DOUT_2-DOUT") (pintype "output"))
    )
    (net (code "41") (name "unconnected-(L25-DIN-Pad4-DIN)") (class "Default")
      (node (ref "L25") (pin "4-DIN") (pinfunction "DIN_4-DIN") (pintype "input"))
    )
    (net (code "42") (name "unconnected-(L28-DOUT-Pad2-DOUT)") (class "Default")
      (node (ref "L28") (pin "2-DOUT") (pinfunction "DOUT_2-DOUT") (pintype "output"))
    )
    (net (code "43") (name "unconnected-(L29-DIN-Pad4-DIN)") (class "Default")
      (node (ref "L29") (pin "4-DIN") (pinfunction "DIN_4-DIN") (pintype "input"))
    )
    (net (code "44") (name "unconnected-(L32-DOUT-Pad2-DOUT)") (class "Default")
      (node (ref "L32") (pin "2-DOUT") (pinfunction "DOUT_2-DOUT") (pintype "output"))
    )
    (net (code "45") (name "unconnected-(U$1-EN-Pad3)") (class "Default")
      (node (ref "U$1") (pin "3") (pinfunction "EN_3") (pintype "bidirectional"))
    )
  )
)
